# OVP.net
KiCad netlist of a schematic drawn in Altium Designer
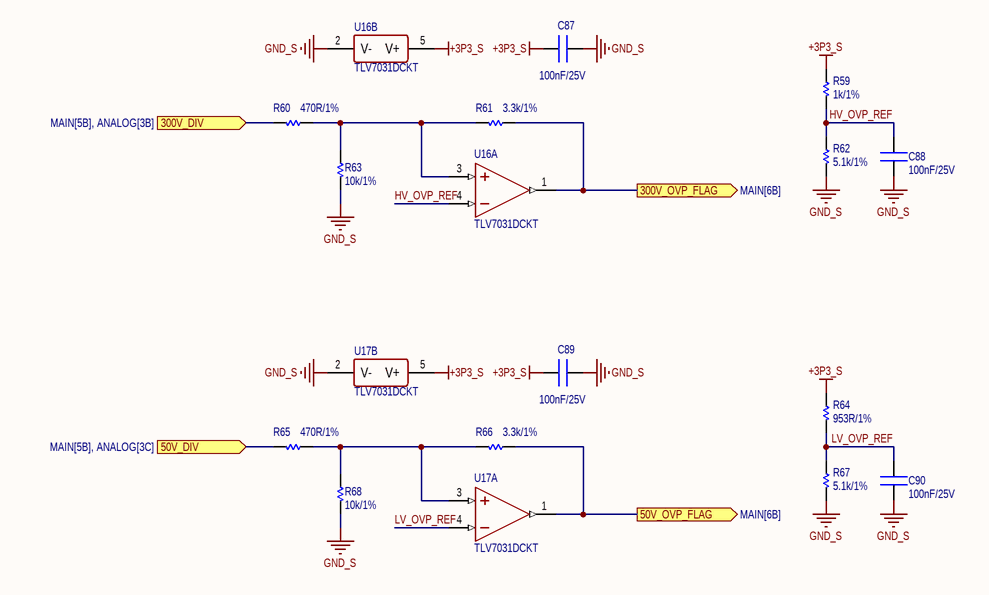
[diagram p0: OVP.SchDoc]

(export (version "E")
  (design (tool "Eeschema 10.0.6"))
  (components
    (comp (ref "C87")
      (value "100nF/25V")
      (footprint "CN-SMD-0603")
      (description "CL10B104KA8NNNC")
      (libsource (lib "Library") (part "CN"))
    )
    (comp (ref "C88")
      (value "100nF/25V")
      (footprint "CN-SMD-0603")
      (description "CL10B104KA8NNNC")
      (libsource (lib "Library") (part "CN"))
    )
    (comp (ref "C89")
      (value "100nF/25V")
      (footprint "CN-SMD-0603")
      (description "CL10B104KA8NNNC")
      (libsource (lib "Library") (part "CN"))
    )
    (comp (ref "C90")
      (value "100nF/25V")
      (footprint "CN-SMD-0603")
      (description "CL10B104KA8NNNC")
      (libsource (lib "Library") (part "CN"))
    )
    (comp (ref "R59")
      (value "1k/1%")
      (footprint "RES-SMD-0603")
      (description "ERJ-3EKF1001V")
      (fields
        (field (name "MANUFACTURER") "Generic Components")
        (field (name "PUBLISHER") "Altium Hobart Technology Centre")
      )
      (libsource (lib "Library") (part "Res-SMD"))
    )
    (comp (ref "R60")
      (value "470R/1%")
      (footprint "RES-SMD-0603")
      (description "ERJ-1GJF4700C")
      (fields
        (field (name "MANUFACTURER") "Generic Components")
        (field (name "PUBLISHER") "Altium Hobart Technology Centre")
      )
      (libsource (lib "Library") (part "Res-SMD"))
    )
    (comp (ref "R61")
      (value "3.3k/1%")
      (footprint "RES-SMD-0603")
      (description "ERJ-3EKF3301V")
      (fields
        (field (name "MANUFACTURER") "Generic Components")
        (field (name "PUBLISHER") "Altium Hobart Technology Centre")
      )
      (libsource (lib "Library") (part "Res-SMD"))
    )
    (comp (ref "R62")
      (value "5.1k/1%")
      (footprint "RES-SMD-0603")
      (description "ERJ-3EKF5101V")
      (fields
        (field (name "MANUFACTURER") "Generic Components")
        (field (name "PUBLISHER") "Altium Hobart Technology Centre")
      )
      (libsource (lib "Library") (part "Res-SMD"))
    )
    (comp (ref "R63")
      (value "10k/1%")
      (footprint "RES-SMD-0603")
      (description "ERJ-3EKF1002V")
      (fields
        (field (name "MANUFACTURER") "Generic Components")
        (field (name "PUBLISHER") "Altium Hobart Technology Centre")
      )
      (libsource (lib "Library") (part "Res-SMD"))
    )
    (comp (ref "R64")
      (value "953R/1%")
      (footprint "RES-SMD-0603")
      (description "ERJ-3EKF9530V")
      (fields
        (field (name "MANUFACTURER") "Generic Components")
        (field (name "PUBLISHER") "Altium Hobart Technology Centre")
      )
      (libsource (lib "Library") (part "Res-SMD"))
    )
    (comp (ref "R65")
      (value "470R/1%")
      (footprint "RES-SMD-0603")
      (description "ERJ-1GJF4700C")
      (fields
        (field (name "MANUFACTURER") "Generic Components")
        (field (name "PUBLISHER") "Altium Hobart Technology Centre")
      )
      (libsource (lib "Library") (part "Res-SMD"))
    )
    (comp (ref "R66")
      (value "3.3k/1%")
      (footprint "RES-SMD-0603")
      (description "ERJ-3EKF3301V")
      (fields
        (field (name "MANUFACTURER") "Generic Components")
        (field (name "PUBLISHER") "Altium Hobart Technology Centre")
      )
      (libsource (lib "Library") (part "Res-SMD"))
    )
    (comp (ref "R67")
      (value "5.1k/1%")
      (footprint "RES-SMD-0603")
      (description "ERJ-3EKF5101V")
      (fields
        (field (name "MANUFACTURER") "Generic Components")
        (field (name "PUBLISHER") "Altium Hobart Technology Centre")
      )
      (libsource (lib "Library") (part "Res-SMD"))
    )
    (comp (ref "R68")
      (value "10k/1%")
      (footprint "RES-SMD-0603")
      (description "ERJ-3EKF1002V")
      (fields
        (field (name "MANUFACTURER") "Generic Components")
        (field (name "PUBLISHER") "Altium Hobart Technology Centre")
      )
      (libsource (lib "Library") (part "Res-SMD"))
    )
    (comp (ref "U16")
      (value "TLV7031DCKT")
      (footprint "SOT353")
      (libsource (lib "Library") (part "OPA340DBV"))
    )
    (comp (ref "U17")
      (value "TLV7031DCKT")
      (footprint "SOT353")
      (libsource (lib "Library") (part "OPA340DBV"))
    )
  )
  (nets
    (net (code "1") (name "+3P3_S") (class "Default")
      (node (ref "C87") (pin "1") (pinfunction "1_1") (pintype "passive"))
      (node (ref "C89") (pin "1") (pinfunction "1_1") (pintype "passive"))
      (node (ref "R59") (pin "1") (pinfunction "1_1") (pintype "passive"))
      (node (ref "R64") (pin "1") (pinfunction "1_1") (pintype "passive"))
      (node (ref "U16") (pin "5") (pinfunction "V+_5") (pintype "passive"))
      (node (ref "U17") (pin "5") (pinfunction "V+_5") (pintype "passive"))
    )
    (net (code "2") (name "/50V_DIV") (class "Default")
      (node (ref "R65") (pin "2") (pinfunction "2_2") (pintype "passive"))
    )
    (net (code "3") (name "/50V_OVP_FLAG") (class "Default")
      (node (ref "R66") (pin "1") (pinfunction "1_1") (pintype "passive"))
      (node (ref "U17") (pin "1") (pinfunction "OUT_1") (pintype "output"))
    )
    (net (code "4") (name "/300V_DIV") (class "Default")
      (node (ref "R60") (pin "2") (pinfunction "2_2") (pintype "passive"))
    )
    (net (code "5") (name "/300V_OVP_FLAG") (class "Default")
      (node (ref "R61") (pin "1") (pinfunction "1_1") (pintype "passive"))
      (node (ref "U16") (pin "1") (pinfunction "OUT_1") (pintype "output"))
    )
    (net (code "6") (name "/HV_OVP_REF") (class "Default")
      (node (ref "C88") (pin "2") (pinfunction "2_2") (pintype "passive"))
      (node (ref "R59") (pin "2") (pinfunction "2_2") (pintype "passive"))
      (node (ref "R62") (pin "1") (pinfunction "1_1") (pintype "passive"))
      (node (ref "U16") (pin "4") (pinfunction "IN-_4") (pintype "input"))
    )
    (net (code "7") (name "/LV_OVP_REF") (class "Default")
      (node (ref "C90") (pin "2") (pinfunction "2_2") (pintype "passive"))
      (node (ref "R64") (pin "2") (pinfunction "2_2") (pintype "passive"))
      (node (ref "R67") (pin "1") (pinfunction "1_1") (pintype "passive"))
      (node (ref "U17") (pin "4") (pinfunction "IN-_4") (pintype "input"))
    )
    (net (code "8") (name "GND_S") (class "Default")
      (node (ref "C87") (pin "2") (pinfunction "2_2") (pintype "passive"))
      (node (ref "C88") (pin "1") (pinfunction "1_1") (pintype "passive"))
      (node (ref "C89") (pin "2") (pinfunction "2_2") (pintype "passive"))
      (node (ref "C90") (pin "1") (pinfunction "1_1") (pintype "passive"))
      (node (ref "R62") (pin "2") (pinfunction "2_2") (pintype "passive"))
      (node (ref "R63") (pin "2") (pinfunction "2_2") (pintype "passive"))
      (node (ref "R67") (pin "2") (pinfunction "2_2") (pintype "passive"))
      (node (ref "R68") (pin "2") (pinfunction "2_2") (pintype "passive"))
      (node (ref "U16") (pin "2") (pinfunction "V-_2") (pintype "passive"))
      (node (ref "U17") (pin "2") (pinfunction "V-_2") (pintype "passive"))
    )
    (net (code "9") (name "Net-(U16A-IN+)") (class "Default")
      (node (ref "R60") (pin "1") (pinfunction "1_1") (pintype "passive"))
      (node (ref "R61") (pin "2") (pinfunction "2_2") (pintype "passive"))
      (node (ref "R63") (pin "1") (pinfunction "1_1") (pintype "passive"))
      (node (ref "U16") (pin "3") (pinfunction "IN+_3") (pintype "input"))
    )
    (net (code "10") (name "Net-(U17A-IN+)") (class "Default")
      (node (ref "R65") (pin "1") (pinfunction "1_1") (pintype "passive"))
      (node (ref "R66") (pin "2") (pinfunction "2_2") (pintype "passive"))
      (node (ref "R68") (pin "1") (pinfunction "1_1") (pintype "passive"))
      (node (ref "U17") (pin "3") (pinfunction "IN+_3") (pintype "input"))
    )
  )
)
